# capelet_gps.net
KiCad netlist of a schematic drawn in EAGLE
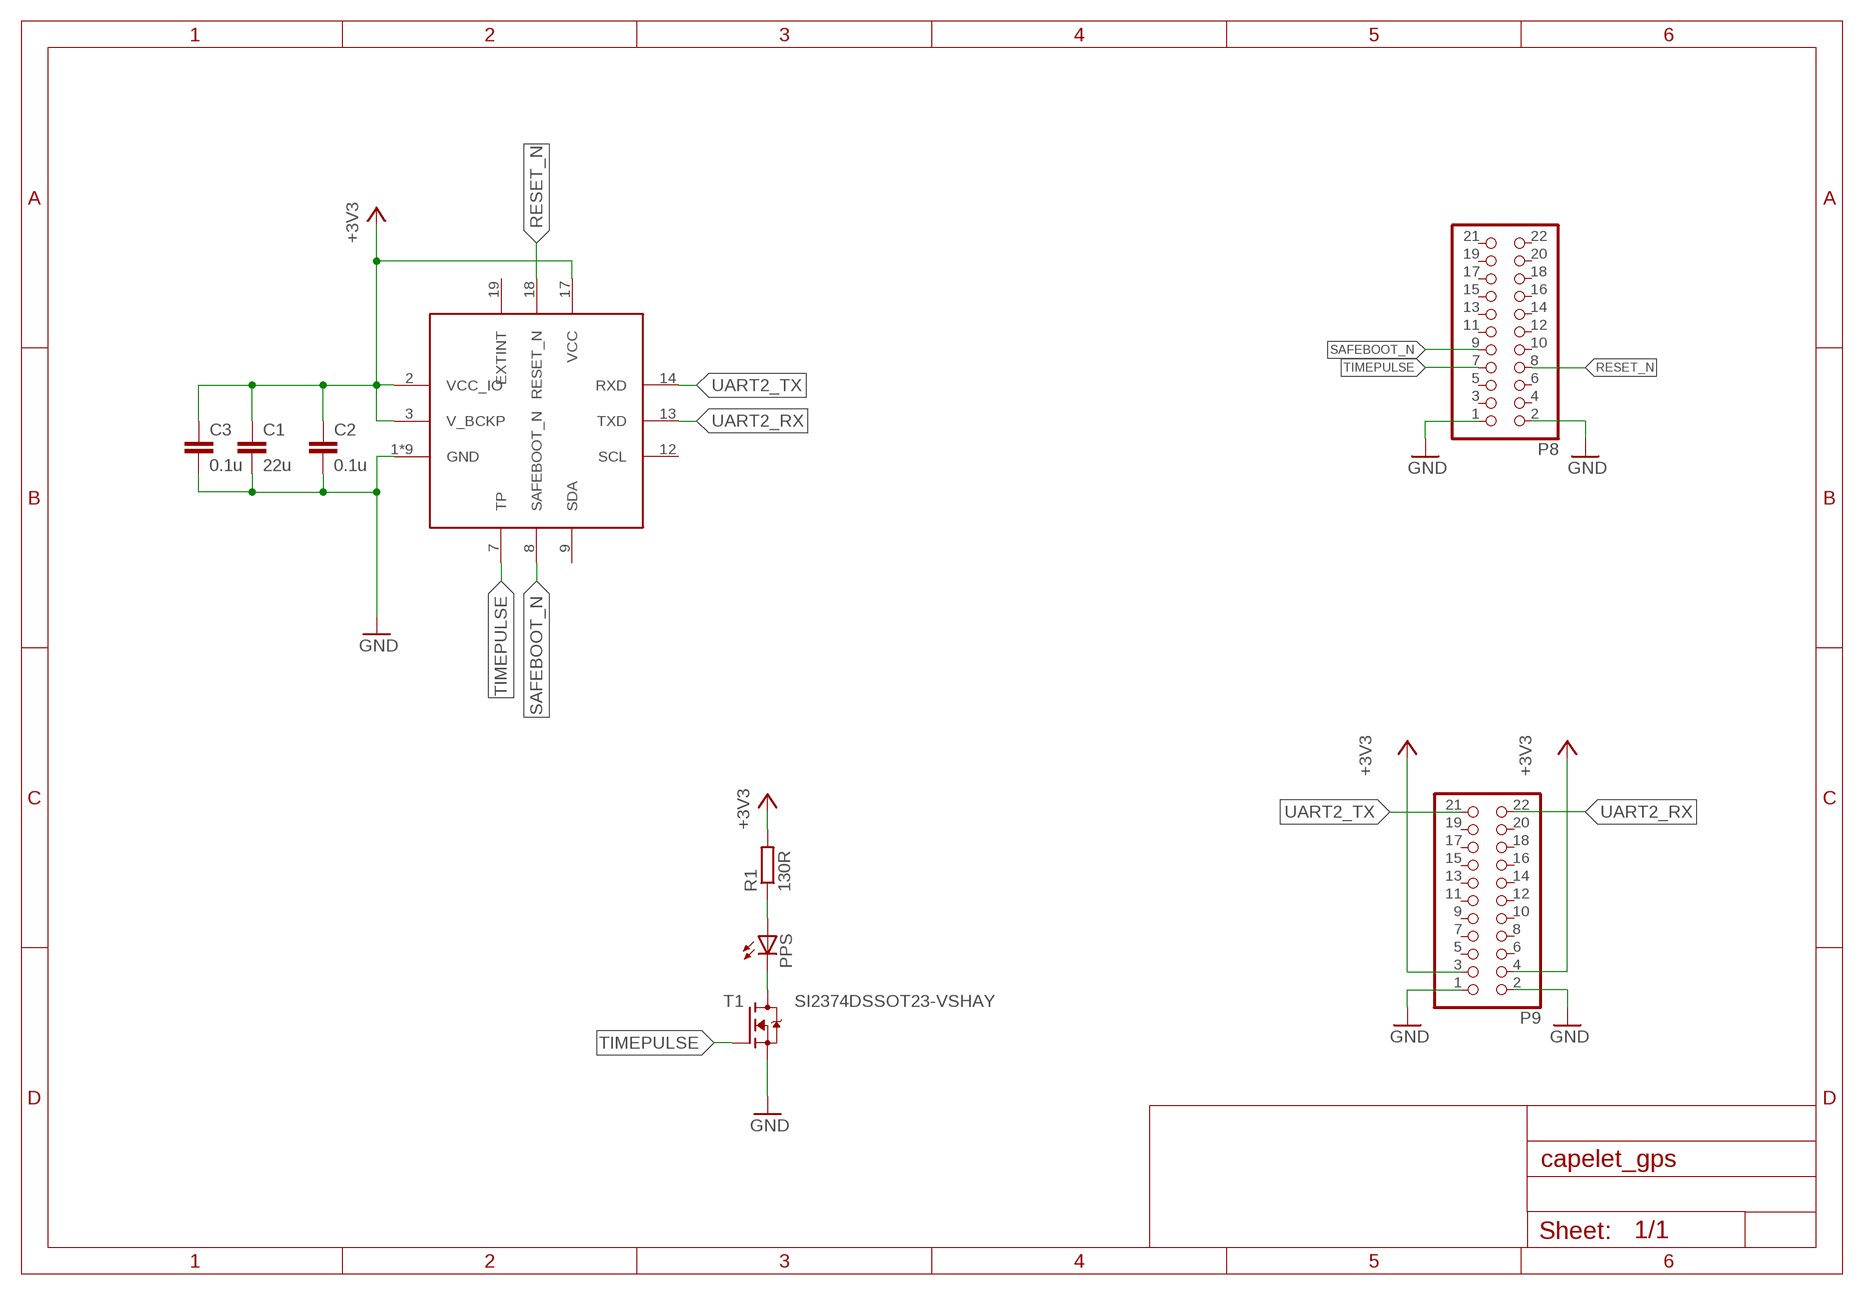
[diagram p0: schematic, sheet 1]

(export (version "E")
  (design (tool "Eeschema 10.0.6"))
  (components
    (comp (ref "C1")
      (value "22u")
      (footprint "eagle-import:CAPC3225X280")
      (libsource (lib "eagle-import") (part "C_SMD1210"))
    )
    (comp (ref "C2")
      (value "0.1u")
      (footprint "eagle-import:CAPC2012X145")
      (libsource (lib "eagle-import") (part "C_SMD0805"))
    )
    (comp (ref "C3")
      (value "0.1u")
      (footprint "eagle-import:CAPC2012X145")
      (libsource (lib "eagle-import") (part "C_SMD0805"))
    )
    (comp (ref "IC1")
      (value "SAM-M8Q")
      (footprint "eagle-import:SAM-M8Q")
      (libsource (lib "eagle-import") (part "SAM-M8Q"))
    )
    (comp (ref "P8")
      (value "PINHD-2X11")
      (footprint "eagle-import:2X11")
      (libsource (lib "eagle-import") (part "PINHD-2X11"))
    )
    (comp (ref "P9")
      (value "PINHD-2X11")
      (footprint "eagle-import:2X11")
      (libsource (lib "eagle-import") (part "PINHD-2X11"))
    )
    (comp (ref "PPS")
      (value "598-8130-107FLED_0805")
      (footprint "eagle-import:LEDC2012X75")
      (libsource (lib "eagle-import") (part "598-8130-107FLED_0805"))
    )
    (comp (ref "R1")
      (value "130R")
      (footprint "eagle-import:RESC2012X65")
      (libsource (lib "eagle-import") (part "R_SMD0805"))
    )
    (comp (ref "T1")
      (value "SI2374DSSOT23-VSHAY")
      (footprint "eagle-import:SOT95P237X112-3")
      (libsource (lib "eagle-import") (part "SI2374DSSOT23-VSHAY"))
    )
  )
  (nets
    (net (code "1") (name "+3V3") (class "Default")
      (node (ref "C1") (pin "1") (pinfunction "1_1") (pintype "passive"))
      (node (ref "C2") (pin "1") (pinfunction "1_1") (pintype "passive"))
      (node (ref "C3") (pin "1") (pinfunction "1_1") (pintype "passive"))
      (node (ref "IC1") (pin "17") (pinfunction "VCC_17") (pintype "bidirectional"))
      (node (ref "IC1") (pin "2") (pinfunction "VCC_IO_2") (pintype "bidirectional"))
      (node (ref "IC1") (pin "3") (pinfunction "V_BCKP_3") (pintype "bidirectional"))
      (node (ref "P9") (pin "3") (pinfunction "4_3") (pintype "passive"))
      (node (ref "P9") (pin "4") (pinfunction "3_4") (pintype "passive"))
      (node (ref "R1") (pin "2") (pinfunction "2_2") (pintype "passive"))
    )
    (net (code "2") (name "GND") (class "Default")
      (node (ref "C1") (pin "2") (pinfunction "2_2") (pintype "passive"))
      (node (ref "C2") (pin "2") (pinfunction "2_2") (pintype "passive"))
      (node (ref "C3") (pin "2") (pinfunction "2_2") (pintype "passive"))
      (node (ref "IC1") (pin "1") (pinfunction "GND_1") (pintype "bidirectional"))
      (node (ref "IC1") (pin "10") (pinfunction "GND_10") (pintype "bidirectional"))
      (node (ref "IC1") (pin "11") (pinfunction "GND_11") (pintype "bidirectional"))
      (node (ref "IC1") (pin "15") (pinfunction "GND_15") (pintype "bidirectional"))
      (node (ref "IC1") (pin "16") (pinfunction "GND_16") (pintype "bidirectional"))
      (node (ref "IC1") (pin "20") (pinfunction "GND_20") (pintype "bidirectional"))
      (node (ref "IC1") (pin "4") (pinfunction "GND_4") (pintype "bidirectional"))
      (node (ref "IC1") (pin "5") (pinfunction "GND_5") (pintype "bidirectional"))
      (node (ref "IC1") (pin "6") (pinfunction "GND_6") (pintype "bidirectional"))
      (node (ref "P8") (pin "1") (pinfunction "2_1") (pintype "passive"))
      (node (ref "P8") (pin "2") (pinfunction "1_2") (pintype "passive"))
      (node (ref "P9") (pin "1") (pinfunction "2_1") (pintype "passive"))
      (node (ref "P9") (pin "2") (pinfunction "1_2") (pintype "passive"))
      (node (ref "T1") (pin "2") (pinfunction "S_2") (pintype "passive"))
    )
    (net (code "3") (name "Net-(PPS-A)") (class "Default")
      (node (ref "PPS") (pin "2") (pinfunction "A_2") (pintype "passive"))
      (node (ref "R1") (pin "1") (pinfunction "1_1") (pintype "passive"))
    )
    (net (code "4") (name "Net-(PPS-C)") (class "Default")
      (node (ref "PPS") (pin "1") (pinfunction "C_1") (pintype "passive"))
      (node (ref "T1") (pin "3") (pinfunction "D_3") (pintype "passive"))
    )
    (net (code "5") (name "RESET_N") (class "Default")
      (node (ref "IC1") (pin "18") (pinfunction "RESET_N_18") (pintype "bidirectional"))
      (node (ref "P8") (pin "8") (pinfunction "7_8") (pintype "passive"))
    )
    (net (code "6") (name "SAFEBOOT_N") (class "Default")
      (node (ref "IC1") (pin "8") (pinfunction "SAFEBOOT_N_8") (pintype "bidirectional"))
      (node (ref "P8") (pin "9") (pinfunction "10_9") (pintype "passive"))
    )
    (net (code "7") (name "TIMEPULSE") (class "Default")
      (node (ref "IC1") (pin "7") (pinfunction "TP_7") (pintype "bidirectional"))
      (node (ref "P8") (pin "7") (pinfunction "8_7") (pintype "passive"))
      (node (ref "T1") (pin "1") (pinfunction "G_1") (pintype "passive"))
    )
    (net (code "8") (name "UART2_RX") (class "Default")
      (node (ref "IC1") (pin "13") (pinfunction "TXD_13") (pintype "bidirectional"))
      (node (ref "P9") (pin "22") (pinfunction "21_22") (pintype "passive"))
    )
    (net (code "9") (name "UART2_TX") (class "Default")
      (node (ref "IC1") (pin "14") (pinfunction "RXD_14") (pintype "bidirectional"))
      (node (ref "P9") (pin "21") (pinfunction "22_21") (pintype "passive"))
    )
    (net (code "10") (name "unconnected-(IC1-EXTINT-Pad19)") (class "Default")
      (node (ref "IC1") (pin "19") (pinfunction "EXTINT_19") (pintype "bidirectional"))
    )
    (net (code "11") (name "unconnected-(IC1-SCL-Pad12)") (class "Default")
      (node (ref "IC1") (pin "12") (pinfunction "SCL_12") (pintype "bidirectional"))
    )
    (net (code "12") (name "unconnected-(IC1-SDA-Pad9)") (class "Default")
      (node (ref "IC1") (pin "9") (pinfunction "SDA_9") (pintype "bidirectional"))
    )
    (net (code "13") (name "unconnected-(P8-3-Pad4)") (class "Default")
      (node (ref "P8") (pin "4") (pinfunction "3_4") (pintype "passive"))
    )
    (net (code "14") (name "unconnected-(P8-4-Pad3)") (class "Default")
      (node (ref "P8") (pin "3") (pinfunction "4_3") (pintype "passive"))
    )
    (net (code "15") (name "unconnected-(P8-5-Pad6)") (class "Default")
      (node (ref "P8") (pin "6") (pinfunction "5_6") (pintype "passive"))
    )
    (net (code "16") (name "unconnected-(P8-6-Pad5)") (class "Default")
      (node (ref "P8") (pin "5") (pinfunction "6_5") (pintype "passive"))
    )
    (net (code "17") (name "unconnected-(P8-9-Pad10)") (class "Default")
      (node (ref "P8") (pin "10") (pinfunction "9_10") (pintype "passive"))
    )
    (net (code "18") (name "unconnected-(P8-11-Pad12)") (class "Default")
      (node (ref "P8") (pin "12") (pinfunction "11_12") (pintype "passive"))
    )
    (net (code "19") (name "unconnected-(P8-12-Pad11)") (class "Default")
      (node (ref "P8") (pin "11") (pinfunction "12_11") (pintype "passive"))
    )
    (net (code "20") (name "unconnected-(P8-13-Pad14)") (class "Default")
      (node (ref "P8") (pin "14") (pinfunction "13_14") (pintype "passive"))
    )
    (net (code "21") (name "unconnected-(P8-14-Pad13)") (class "Default")
      (node (ref "P8") (pin "13") (pinfunction "14_13") (pintype "passive"))
    )
    (net (code "22") (name "unconnected-(P8-15-Pad16)") (class "Default")
      (node (ref "P8") (pin "16") (pinfunction "15_16") (pintype "passive"))
    )
    (net (code "23") (name "unconnected-(P8-16-Pad15)") (class "Default")
      (node (ref "P8") (pin "15") (pinfunction "16_15") (pintype "passive"))
    )
    (net (code "24") (name "unconnected-(P8-17-Pad18)") (class "Default")
      (node (ref "P8") (pin "18") (pinfunction "17_18") (pintype "passive"))
    )
    (net (code "25") (name "unconnected-(P8-18-Pad17)") (class "Default")
      (node (ref "P8") (pin "17") (pinfunction "18_17") (pintype "passive"))
    )
    (net (code "26") (name "unconnected-(P8-19-Pad20)") (class "Default")
      (node (ref "P8") (pin "20") (pinfunction "19_20") (pintype "passive"))
    )
    (net (code "27") (name "unconnected-(P8-20-Pad19)") (class "Default")
      (node (ref "P8") (pin "19") (pinfunction "20_19") (pintype "passive"))
    )
    (net (code "28") (name "unconnected-(P8-21-Pad22)") (class "Default")
      (node (ref "P8") (pin "22") (pinfunction "21_22") (pintype "passive"))
    )
    (net (code "29") (name "unconnected-(P8-22-Pad21)") (class "Default")
      (node (ref "P8") (pin "21") (pinfunction "22_21") (pintype "passive"))
    )
    (net (code "30") (name "unconnected-(P9-5-Pad6)") (class "Default")
      (node (ref "P9") (pin "6") (pinfunction "5_6") (pintype "passive"))
    )
    (net (code "31") (name "unconnected-(P9-6-Pad5)") (class "Default")
      (node (ref "P9") (pin "5") (pinfunction "6_5") (pintype "passive"))
    )
    (net (code "32") (name "unconnected-(P9-7-Pad8)") (class "Default")
      (node (ref "P9") (pin "8") (pinfunction "7_8") (pintype "passive"))
    )
    (net (code "33") (name "unconnected-(P9-8-Pad7)") (class "Default")
      (node (ref "P9") (pin "7") (pinfunction "8_7") (pintype "passive"))
    )
    (net (code "34") (name "unconnected-(P9-9-Pad10)") (class "Default")
      (node (ref "P9") (pin "10") (pinfunction "9_10") (pintype "passive"))
    )
    (net (code "35") (name "unconnected-(P9-10-Pad9)") (class "Default")
      (node (ref "P9") (pin "9") (pinfunction "10_9") (pintype "passive"))
    )
    (net (code "36") (name "unconnected-(P9-11-Pad12)") (class "Default")
      (node (ref "P9") (pin "12") (pinfunction "11_12") (pintype "passive"))
    )
    (net (code "37") (name "unconnected-(P9-12-Pad11)") (class "Default")
      (node (ref "P9") (pin "11") (pinfunction "12_11") (pintype "passive"))
    )
    (net (code "38") (name "unconnected-(P9-13-Pad14)") (class "Default")
      (node (ref "P9") (pin "14") (pinfunction "13_14") (pintype "passive"))
    )
    (net (code "39") (name "unconnected-(P9-14-Pad13)") (class "Default")
      (node (ref "P9") (pin "13") (pinfunction "14_13") (pintype "passive"))
    )
    (net (code "40") (name "unconnected-(P9-15-Pad16)") (class "Default")
      (node (ref "P9") (pin "16") (pinfunction "15_16") (pintype "passive"))
    )
    (net (code "41") (name "unconnected-(P9-16-Pad15)") (class "Default")
      (node (ref "P9") (pin "15") (pinfunction "16_15") (pintype "passive"))
    )
    (net (code "42") (name "unconnected-(P9-17-Pad18)") (class "Default")
      (node (ref "P9") (pin "18") (pinfunction "17_18") (pintype "passive"))
    )
    (net (code "43") (name "unconnected-(P9-18-Pad17)") (class "Default")
      (node (ref "P9") (pin "17") (pinfunction "18_17") (pintype "passive"))
    )
    (net (code "44") (name "unconnected-(P9-19-Pad20)") (class "Default")
      (node (ref "P9") (pin "20") (pinfunction "19_20") (pintype "passive"))
    )
    (net (code "45") (name "unconnected-(P9-20-Pad19)") (class "Default")
      (node (ref "P9") (pin "19") (pinfunction "20_19") (pintype "passive"))
    )
  )
)
